# tick-display-mk-2_2-mini.net
KiCad netlist of a schematic drawn in EAGLE
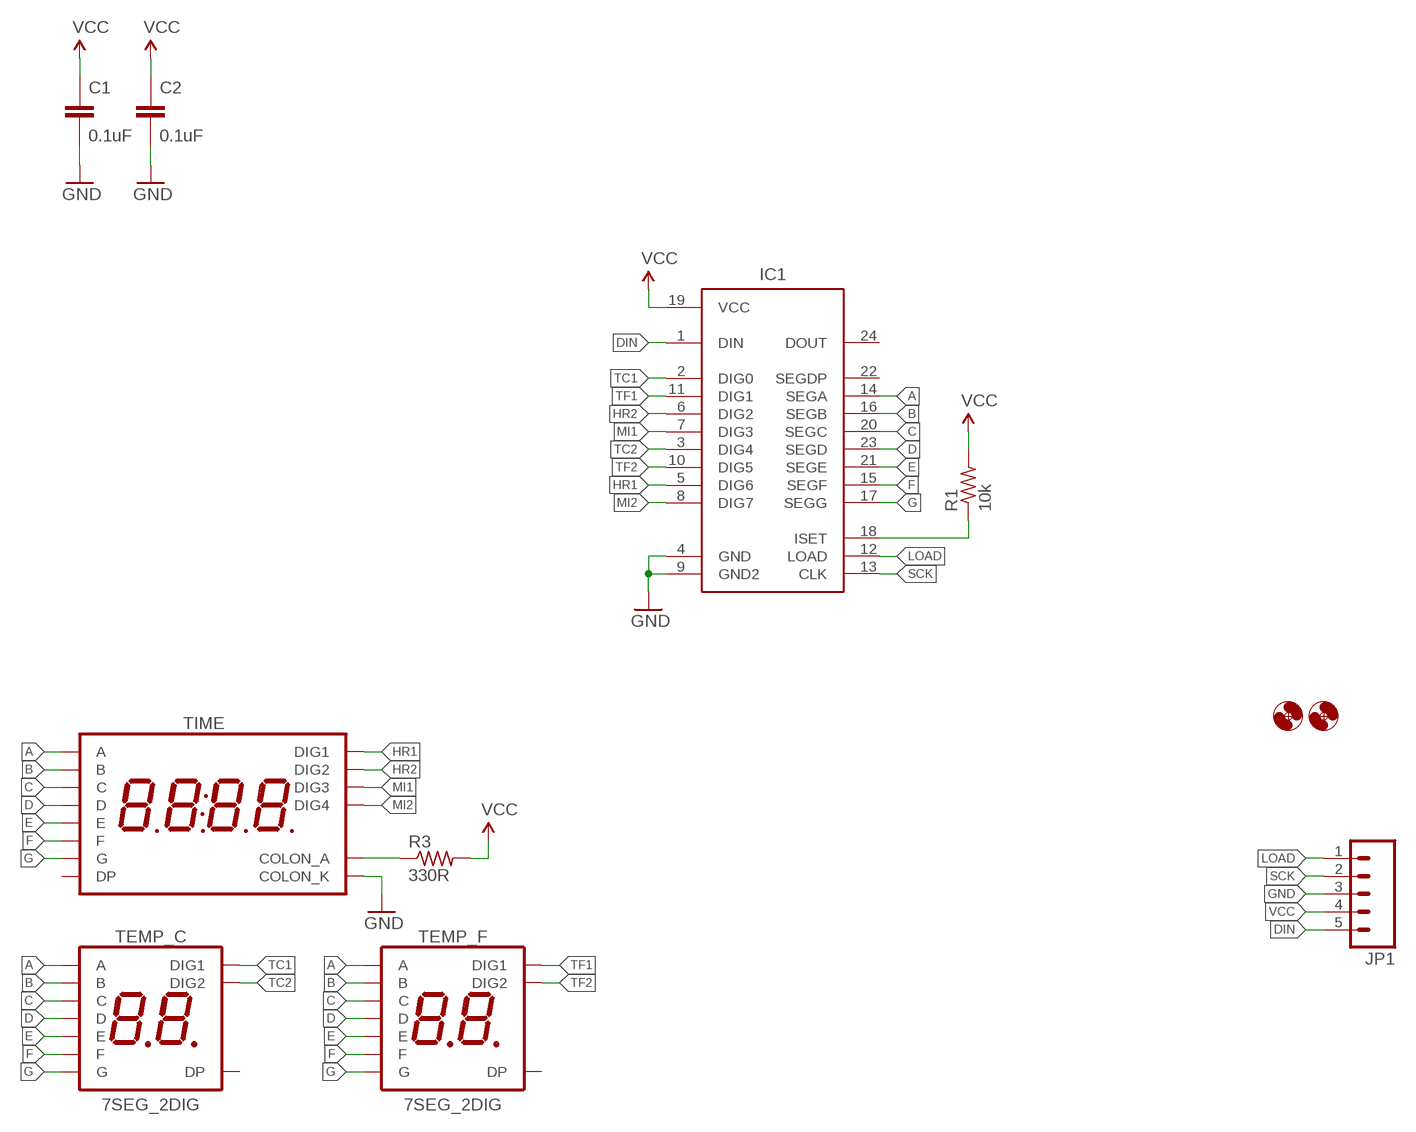
[diagram p0: schematic, sheet 1]

(export (version "E")
  (design (tool "Eeschema 10.0.6"))
  (components
    (comp (ref "C1")
      (value "0.1uF")
      (footprint "eagle-import:C025-024X044")
      (libsource (lib "eagle-import") (part "CAPACITOR-CERAMIC025-024X044"))
    )
    (comp (ref "C2")
      (value "0.1uF")
      (footprint "eagle-import:C025-024X044")
      (libsource (lib "eagle-import") (part "CAPACITOR-CERAMIC025-024X044"))
    )
    (comp (ref "H3")
      (value "HOLE#2")
      (footprint "eagle-import:HOLE-#2")
      (libsource (lib "eagle-import") (part "HOLE#2"))
    )
    (comp (ref "H4")
      (value "HOLE#2")
      (footprint "eagle-import:HOLE-#2")
      (libsource (lib "eagle-import") (part "HOLE#2"))
    )
    (comp (ref "IC1")
      (value "MAX7219DIP")
      (footprint "eagle-import:DIL24")
      (libsource (lib "eagle-import") (part "MAX7219DIP"))
    )
    (comp (ref "JP1")
      (value "M05JST-PH-VERT-PTH")
      (footprint "eagle-import:JST-5-PH-VERT-PTH")
      (libsource (lib "eagle-import") (part "M05JST-PH-VERT-PTH"))
    )
    (comp (ref "R1")
      (value "10k")
      (footprint "eagle-import:RESISTOR-AXIAL-PTH-5.08MM")
      (libsource (lib "eagle-import") (part "RESISTORPTH-AXIAL-5.08MM"))
    )
    (comp (ref "R3")
      (value "330R")
      (footprint "eagle-import:RESISTOR-AXIAL-PTH-5.08MM")
      (libsource (lib "eagle-import") (part "RESISTORPTH-AXIAL-5.08MM"))
    )
    (comp (ref "TEMP_C")
      (value "7SEG_2DIG")
      (footprint "eagle-import:7SEG_2DIG_14MM")
      (libsource (lib "eagle-import") (part "7SEG_2DIG"))
    )
    (comp (ref "TEMP_F")
      (value "7SEG_2DIG")
      (footprint "eagle-import:7SEG_2DIG_14MM")
      (libsource (lib "eagle-import") (part "7SEG_2DIG"))
    )
    (comp (ref "TIME")
      (value "7SED_4DIGIT_14MM14.2MM-CC")
      (footprint "eagle-import:7SEG_4DIG")
      (libsource (lib "eagle-import") (part "7SED_4DIGIT_14MM14.2MM-CC"))
    )
  )
  (nets
    (net (code "1") (name "A") (class "Default")
      (node (ref "IC1") (pin "14") (pinfunction "SEGA_14") (pintype "bidirectional"))
      (node (ref "TEMP_C") (pin "4") (pinfunction "A_4") (pintype "passive"))
      (node (ref "TEMP_F") (pin "4") (pinfunction "A_4") (pintype "passive"))
      (node (ref "TIME") (pin "P$13") (pinfunction "A_P$13") (pintype "passive"))
    )
    (net (code "2") (name "B") (class "Default")
      (node (ref "IC1") (pin "16") (pinfunction "SEGB_16") (pintype "bidirectional"))
      (node (ref "TEMP_C") (pin "3") (pinfunction "B_3") (pintype "passive"))
      (node (ref "TEMP_F") (pin "3") (pinfunction "B_3") (pintype "passive"))
      (node (ref "TIME") (pin "P$9") (pinfunction "B_P$9") (pintype "passive"))
    )
    (net (code "3") (name "C") (class "Default")
      (node (ref "IC1") (pin "20") (pinfunction "SEGC_20") (pintype "bidirectional"))
      (node (ref "TEMP_C") (pin "9") (pinfunction "C_9") (pintype "passive"))
      (node (ref "TEMP_F") (pin "9") (pinfunction "C_9") (pintype "passive"))
      (node (ref "TIME") (pin "P$4") (pinfunction "C_P$4") (pintype "passive"))
    )
    (net (code "4") (name "D") (class "Default")
      (node (ref "IC1") (pin "23") (pinfunction "SEGD_23") (pintype "bidirectional"))
      (node (ref "TEMP_C") (pin "8") (pinfunction "D_8") (pintype "passive"))
      (node (ref "TEMP_F") (pin "8") (pinfunction "D_8") (pintype "passive"))
      (node (ref "TIME") (pin "P$2") (pinfunction "D_P$2") (pintype "passive"))
    )
    (net (code "5") (name "DIN") (class "Default")
      (node (ref "IC1") (pin "1") (pinfunction "DIN_1") (pintype "bidirectional"))
      (node (ref "JP1") (pin "5") (pinfunction "5_5") (pintype "passive"))
    )
    (net (code "6") (name "E") (class "Default")
      (node (ref "IC1") (pin "21") (pinfunction "SEGE_21") (pintype "bidirectional"))
      (node (ref "TEMP_C") (pin "6") (pinfunction "E_6") (pintype "passive"))
      (node (ref "TEMP_F") (pin "6") (pinfunction "E_6") (pintype "passive"))
      (node (ref "TIME") (pin "P$1") (pinfunction "E_P$1") (pintype "passive"))
    )
    (net (code "7") (name "F") (class "Default")
      (node (ref "IC1") (pin "15") (pinfunction "SEGF_15") (pintype "bidirectional"))
      (node (ref "TEMP_C") (pin "7") (pinfunction "F_7") (pintype "passive"))
      (node (ref "TEMP_F") (pin "7") (pinfunction "F_7") (pintype "passive"))
      (node (ref "TIME") (pin "P$12") (pinfunction "F_P$12") (pintype "passive"))
    )
    (net (code "8") (name "G") (class "Default")
      (node (ref "IC1") (pin "17") (pinfunction "SEGG_17") (pintype "bidirectional"))
      (node (ref "TEMP_C") (pin "1") (pinfunction "G_1") (pintype "passive"))
      (node (ref "TEMP_F") (pin "1") (pinfunction "G_1") (pintype "passive"))
      (node (ref "TIME") (pin "P$5") (pinfunction "G_P$5") (pintype "passive"))
    )
    (net (code "9") (name "GND") (class "Default")
      (node (ref "C1") (pin "2") (pinfunction "2_2") (pintype "passive"))
      (node (ref "C2") (pin "2") (pinfunction "2_2") (pintype "passive"))
      (node (ref "IC1") (pin "4") (pinfunction "GND_4") (pintype "bidirectional"))
      (node (ref "IC1") (pin "9") (pinfunction "GND2_9") (pintype "bidirectional"))
      (node (ref "JP1") (pin "3") (pinfunction "3_3") (pintype "passive"))
      (node (ref "TIME") (pin "P$7") (pinfunction "COLON_K_P$7") (pintype "passive"))
    )
    (net (code "10") (name "HR1") (class "Default")
      (node (ref "IC1") (pin "5") (pinfunction "DIG6_5") (pintype "bidirectional"))
      (node (ref "TIME") (pin "P$14") (pinfunction "DIG1_P$14") (pintype "passive"))
    )
    (net (code "11") (name "HR2") (class "Default")
      (node (ref "IC1") (pin "6") (pinfunction "DIG2_6") (pintype "bidirectional"))
      (node (ref "TIME") (pin "P$11") (pinfunction "DIG2_P$11") (pintype "passive"))
    )
    (net (code "12") (name "LOAD") (class "Default")
      (node (ref "IC1") (pin "12") (pinfunction "LOAD_12") (pintype "bidirectional"))
      (node (ref "JP1") (pin "1") (pinfunction "1_1") (pintype "passive"))
    )
    (net (code "13") (name "MI1") (class "Default")
      (node (ref "IC1") (pin "7") (pinfunction "DIG3_7") (pintype "bidirectional"))
      (node (ref "TIME") (pin "P$10") (pinfunction "DIG3_P$10") (pintype "passive"))
    )
    (net (code "14") (name "MI2") (class "Default")
      (node (ref "IC1") (pin "8") (pinfunction "DIG7_8") (pintype "bidirectional"))
      (node (ref "TIME") (pin "P$6") (pinfunction "DIG4_P$6") (pintype "passive"))
    )
    (net (code "15") (name "Net-(IC1-ISET)") (class "Default")
      (node (ref "IC1") (pin "18") (pinfunction "ISET_18") (pintype "bidirectional"))
      (node (ref "R1") (pin "P$1") (pinfunction "1_P$1") (pintype "passive"))
    )
    (net (code "16") (name "Net-(R3-1)") (class "Default")
      (node (ref "R3") (pin "P$1") (pinfunction "1_P$1") (pintype "passive"))
      (node (ref "TIME") (pin "P$8") (pinfunction "COLON_A_P$8") (pintype "passive"))
    )
    (net (code "17") (name "SCK") (class "Default")
      (node (ref "IC1") (pin "13") (pinfunction "CLK_13") (pintype "bidirectional"))
      (node (ref "JP1") (pin "2") (pinfunction "2_2") (pintype "passive"))
    )
    (net (code "18") (name "TC1") (class "Default")
      (node (ref "IC1") (pin "2") (pinfunction "DIG0_2") (pintype "bidirectional"))
      (node (ref "TEMP_C") (pin "5") (pinfunction "DIG1_5") (pintype "passive"))
    )
    (net (code "19") (name "TC2") (class "Default")
      (node (ref "IC1") (pin "3") (pinfunction "DIG4_3") (pintype "bidirectional"))
      (node (ref "TEMP_C") (pin "10") (pinfunction "DIG2_10") (pintype "passive"))
    )
    (net (code "20") (name "TF1") (class "Default")
      (node (ref "IC1") (pin "11") (pinfunction "DIG1_11") (pintype "bidirectional"))
      (node (ref "TEMP_F") (pin "5") (pinfunction "DIG1_5") (pintype "passive"))
    )
    (net (code "21") (name "TF2") (class "Default")
      (node (ref "IC1") (pin "10") (pinfunction "DIG5_10") (pintype "bidirectional"))
      (node (ref "TEMP_F") (pin "10") (pinfunction "DIG2_10") (pintype "passive"))
    )
    (net (code "22") (name "VCC") (class "Default")
      (node (ref "C1") (pin "1") (pinfunction "1_1") (pintype "passive"))
      (node (ref "C2") (pin "1") (pinfunction "1_1") (pintype "passive"))
      (node (ref "IC1") (pin "19") (pinfunction "VCC_19") (pintype "bidirectional"))
      (node (ref "JP1") (pin "4") (pinfunction "4_4") (pintype "passive"))
      (node (ref "R1") (pin "P$2") (pinfunction "2_P$2") (pintype "passive"))
      (node (ref "R3") (pin "P$2") (pinfunction "2_P$2") (pintype "passive"))
    )
    (net (code "23") (name "unconnected-(IC1-DOUT-Pad24)") (class "Default")
      (node (ref "IC1") (pin "24") (pinfunction "DOUT_24") (pintype "bidirectional"))
    )
    (net (code "24") (name "unconnected-(IC1-SEGDP-Pad22)") (class "Default")
      (node (ref "IC1") (pin "22") (pinfunction "SEGDP_22") (pintype "bidirectional"))
    )
    (net (code "25") (name "unconnected-(TEMP_C-DP-Pad2)") (class "Default")
      (node (ref "TEMP_C") (pin "2") (pinfunction "DP_2") (pintype "passive"))
    )
    (net (code "26") (name "unconnected-(TEMP_F-DP-Pad2)") (class "Default")
      (node (ref "TEMP_F") (pin "2") (pinfunction "DP_2") (pintype "passive"))
    )
    (net (code "27") (name "unconnected-(TIME-DP-PadP$3)") (class "Default")
      (node (ref "TIME") (pin "P$3") (pinfunction "DP_P$3") (pintype "passive"))
    )
  )
)
